# BUTTON_BREAKOUT.net
KiCad netlist of a schematic drawn in EAGLE
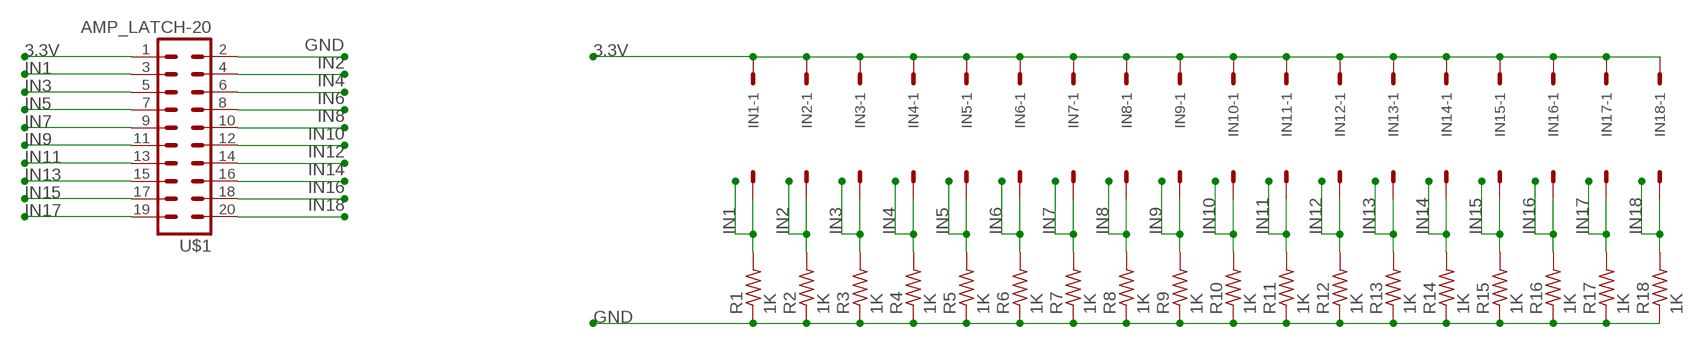
[diagram p0: schematic, sheet 1]

(export (version "E")
  (design (tool "Eeschema 10.0.6"))
  (components
    (comp (ref "IN1")
      (value "C-GRID-02-70543")
      (footprint "eagle-import:70543-02")
      (libsource (lib "eagle-import") (part "C-GRID-02-70543"))
    )
    (comp (ref "IN2")
      (value "C-GRID-02-70543")
      (footprint "eagle-import:70543-02")
      (libsource (lib "eagle-import") (part "C-GRID-02-70543"))
    )
    (comp (ref "IN3")
      (value "C-GRID-02-70543")
      (footprint "eagle-import:70543-02")
      (libsource (lib "eagle-import") (part "C-GRID-02-70543"))
    )
    (comp (ref "IN4")
      (value "C-GRID-02-70543")
      (footprint "eagle-import:70543-02")
      (libsource (lib "eagle-import") (part "C-GRID-02-70543"))
    )
    (comp (ref "IN5")
      (value "C-GRID-02-70543")
      (footprint "eagle-import:70543-02")
      (libsource (lib "eagle-import") (part "C-GRID-02-70543"))
    )
    (comp (ref "IN6")
      (value "C-GRID-02-70543")
      (footprint "eagle-import:70543-02")
      (libsource (lib "eagle-import") (part "C-GRID-02-70543"))
    )
    (comp (ref "IN7")
      (value "C-GRID-02-70543")
      (footprint "eagle-import:70543-02")
      (libsource (lib "eagle-import") (part "C-GRID-02-70543"))
    )
    (comp (ref "IN8")
      (value "C-GRID-02-70543")
      (footprint "eagle-import:70543-02")
      (libsource (lib "eagle-import") (part "C-GRID-02-70543"))
    )
    (comp (ref "IN9")
      (value "C-GRID-02-70543")
      (footprint "eagle-import:70543-02")
      (libsource (lib "eagle-import") (part "C-GRID-02-70543"))
    )
    (comp (ref "IN10")
      (value "C-GRID-02-70543")
      (footprint "eagle-import:70543-02")
      (libsource (lib "eagle-import") (part "C-GRID-02-70543"))
    )
    (comp (ref "IN11")
      (value "C-GRID-02-70543")
      (footprint "eagle-import:70543-02")
      (libsource (lib "eagle-import") (part "C-GRID-02-70543"))
    )
    (comp (ref "IN12")
      (value "C-GRID-02-70543")
      (footprint "eagle-import:70543-02")
      (libsource (lib "eagle-import") (part "C-GRID-02-70543"))
    )
    (comp (ref "IN13")
      (value "C-GRID-02-70543")
      (footprint "eagle-import:70543-02")
      (libsource (lib "eagle-import") (part "C-GRID-02-70543"))
    )
    (comp (ref "IN14")
      (value "C-GRID-02-70543")
      (footprint "eagle-import:70543-02")
      (libsource (lib "eagle-import") (part "C-GRID-02-70543"))
    )
    (comp (ref "IN15")
      (value "C-GRID-02-70543")
      (footprint "eagle-import:70543-02")
      (libsource (lib "eagle-import") (part "C-GRID-02-70543"))
    )
    (comp (ref "IN16")
      (value "C-GRID-02-70543")
      (footprint "eagle-import:70543-02")
      (libsource (lib "eagle-import") (part "C-GRID-02-70543"))
    )
    (comp (ref "IN17")
      (value "C-GRID-02-70543")
      (footprint "eagle-import:70543-02")
      (libsource (lib "eagle-import") (part "C-GRID-02-70543"))
    )
    (comp (ref "IN18")
      (value "C-GRID-02-70543")
      (footprint "eagle-import:70543-02")
      (libsource (lib "eagle-import") (part "C-GRID-02-70543"))
    )
    (comp (ref "R1")
      (value "1K")
      (footprint "eagle-import:R1206")
      (libsource (lib "eagle-import") (part "R-US_R1206"))
    )
    (comp (ref "R2")
      (value "1K")
      (footprint "eagle-import:R1206")
      (libsource (lib "eagle-import") (part "R-US_R1206"))
    )
    (comp (ref "R3")
      (value "1K")
      (footprint "eagle-import:R1206")
      (libsource (lib "eagle-import") (part "R-US_R1206"))
    )
    (comp (ref "R4")
      (value "1K")
      (footprint "eagle-import:R1206")
      (libsource (lib "eagle-import") (part "R-US_R1206"))
    )
    (comp (ref "R5")
      (value "1K")
      (footprint "eagle-import:R1206")
      (libsource (lib "eagle-import") (part "R-US_R1206"))
    )
    (comp (ref "R6")
      (value "1K")
      (footprint "eagle-import:R1206")
      (libsource (lib "eagle-import") (part "R-US_R1206"))
    )
    (comp (ref "R7")
      (value "1K")
      (footprint "eagle-import:R1206")
      (libsource (lib "eagle-import") (part "R-US_R1206"))
    )
    (comp (ref "R8")
      (value "1K")
      (footprint "eagle-import:R1206")
      (libsource (lib "eagle-import") (part "R-US_R1206"))
    )
    (comp (ref "R9")
      (value "1K")
      (footprint "eagle-import:R1206")
      (libsource (lib "eagle-import") (part "R-US_R1206"))
    )
    (comp (ref "R10")
      (value "1K")
      (footprint "eagle-import:R1206")
      (libsource (lib "eagle-import") (part "R-US_R1206"))
    )
    (comp (ref "R11")
      (value "1K")
      (footprint "eagle-import:R1206")
      (libsource (lib "eagle-import") (part "R-US_R1206"))
    )
    (comp (ref "R12")
      (value "1K")
      (footprint "eagle-import:R1206")
      (libsource (lib "eagle-import") (part "R-US_R1206"))
    )
    (comp (ref "R13")
      (value "1K")
      (footprint "eagle-import:R1206")
      (libsource (lib "eagle-import") (part "R-US_R1206"))
    )
    (comp (ref "R14")
      (value "1K")
      (footprint "eagle-import:R1206")
      (libsource (lib "eagle-import") (part "R-US_R1206"))
    )
    (comp (ref "R15")
      (value "1K")
      (footprint "eagle-import:R1206")
      (libsource (lib "eagle-import") (part "R-US_R1206"))
    )
    (comp (ref "R16")
      (value "1K")
      (footprint "eagle-import:R1206")
      (libsource (lib "eagle-import") (part "R-US_R1206"))
    )
    (comp (ref "R17")
      (value "1K")
      (footprint "eagle-import:R1206")
      (libsource (lib "eagle-import") (part "R-US_R1206"))
    )
    (comp (ref "R18")
      (value "1K")
      (footprint "eagle-import:R1206")
      (libsource (lib "eagle-import") (part "R-US_R1206"))
    )
    (comp (ref "U$1")
      (value "AMP_LATCH-20")
      (footprint "eagle-import:MA10-2")
      (fields (field (name "PART_NUM") "5499160-1"))
      (libsource (lib "eagle-import") (part "AMP_LATCH-20"))
    )
  )
  (nets
    (net (code "1") (name "/3.3V") (class "Default")
      (node (ref "IN1") (pin "1") (pinfunction "S_1") (pintype "passive"))
      (node (ref "IN10") (pin "1") (pinfunction "S_1") (pintype "passive"))
      (node (ref "IN11") (pin "1") (pinfunction "S_1") (pintype "passive"))
      (node (ref "IN12") (pin "1") (pinfunction "S_1") (pintype "passive"))
      (node (ref "IN13") (pin "1") (pinfunction "S_1") (pintype "passive"))
      (node (ref "IN14") (pin "1") (pinfunction "S_1") (pintype "passive"))
      (node (ref "IN15") (pin "1") (pinfunction "S_1") (pintype "passive"))
      (node (ref "IN16") (pin "1") (pinfunction "S_1") (pintype "passive"))
      (node (ref "IN17") (pin "1") (pinfunction "S_1") (pintype "passive"))
      (node (ref "IN18") (pin "1") (pinfunction "S_1") (pintype "passive"))
      (node (ref "IN2") (pin "1") (pinfunction "S_1") (pintype "passive"))
      (node (ref "IN3") (pin "1") (pinfunction "S_1") (pintype "passive"))
      (node (ref "IN4") (pin "1") (pinfunction "S_1") (pintype "passive"))
      (node (ref "IN5") (pin "1") (pinfunction "S_1") (pintype "passive"))
      (node (ref "IN6") (pin "1") (pinfunction "S_1") (pintype "passive"))
      (node (ref "IN7") (pin "1") (pinfunction "S_1") (pintype "passive"))
      (node (ref "IN8") (pin "1") (pinfunction "S_1") (pintype "passive"))
      (node (ref "IN9") (pin "1") (pinfunction "S_1") (pintype "passive"))
      (node (ref "U$1") (pin "1") (pinfunction "1_1") (pintype "passive"))
    )
    (net (code "2") (name "/GND") (class "Default")
      (node (ref "R1") (pin "1") (pinfunction "1_1") (pintype "passive"))
      (node (ref "R10") (pin "1") (pinfunction "1_1") (pintype "passive"))
      (node (ref "R11") (pin "1") (pinfunction "1_1") (pintype "passive"))
      (node (ref "R12") (pin "1") (pinfunction "1_1") (pintype "passive"))
      (node (ref "R13") (pin "1") (pinfunction "1_1") (pintype "passive"))
      (node (ref "R14") (pin "1") (pinfunction "1_1") (pintype "passive"))
      (node (ref "R15") (pin "1") (pinfunction "1_1") (pintype "passive"))
      (node (ref "R16") (pin "1") (pinfunction "1_1") (pintype "passive"))
      (node (ref "R17") (pin "1") (pinfunction "1_1") (pintype "passive"))
      (node (ref "R18") (pin "1") (pinfunction "1_1") (pintype "passive"))
      (node (ref "R2") (pin "1") (pinfunction "1_1") (pintype "passive"))
      (node (ref "R3") (pin "1") (pinfunction "1_1") (pintype "passive"))
      (node (ref "R4") (pin "1") (pinfunction "1_1") (pintype "passive"))
      (node (ref "R5") (pin "1") (pinfunction "1_1") (pintype "passive"))
      (node (ref "R6") (pin "1") (pinfunction "1_1") (pintype "passive"))
      (node (ref "R7") (pin "1") (pinfunction "1_1") (pintype "passive"))
      (node (ref "R8") (pin "1") (pinfunction "1_1") (pintype "passive"))
      (node (ref "R9") (pin "1") (pinfunction "1_1") (pintype "passive"))
      (node (ref "U$1") (pin "2") (pinfunction "2_2") (pintype "passive"))
    )
    (net (code "3") (name "/IN1") (class "Default")
      (node (ref "IN1") (pin "2") (pinfunction "S_2") (pintype "passive"))
      (node (ref "R1") (pin "2") (pinfunction "2_2") (pintype "passive"))
      (node (ref "U$1") (pin "3") (pinfunction "3_3") (pintype "passive"))
    )
    (net (code "4") (name "/IN2") (class "Default")
      (node (ref "IN2") (pin "2") (pinfunction "S_2") (pintype "passive"))
      (node (ref "R2") (pin "2") (pinfunction "2_2") (pintype "passive"))
      (node (ref "U$1") (pin "4") (pinfunction "4_4") (pintype "passive"))
    )
    (net (code "5") (name "/IN3") (class "Default")
      (node (ref "IN3") (pin "2") (pinfunction "S_2") (pintype "passive"))
      (node (ref "R3") (pin "2") (pinfunction "2_2") (pintype "passive"))
      (node (ref "U$1") (pin "5") (pinfunction "5_5") (pintype "passive"))
    )
    (net (code "6") (name "/IN4") (class "Default")
      (node (ref "IN4") (pin "2") (pinfunction "S_2") (pintype "passive"))
      (node (ref "R4") (pin "2") (pinfunction "2_2") (pintype "passive"))
      (node (ref "U$1") (pin "6") (pinfunction "6_6") (pintype "passive"))
    )
    (net (code "7") (name "/IN5") (class "Default")
      (node (ref "IN5") (pin "2") (pinfunction "S_2") (pintype "passive"))
      (node (ref "R5") (pin "2") (pinfunction "2_2") (pintype "passive"))
      (node (ref "U$1") (pin "7") (pinfunction "7_7") (pintype "passive"))
    )
    (net (code "8") (name "/IN6") (class "Default")
      (node (ref "IN6") (pin "2") (pinfunction "S_2") (pintype "passive"))
      (node (ref "R6") (pin "2") (pinfunction "2_2") (pintype "passive"))
      (node (ref "U$1") (pin "8") (pinfunction "8_8") (pintype "passive"))
    )
    (net (code "9") (name "/IN7") (class "Default")
      (node (ref "IN7") (pin "2") (pinfunction "S_2") (pintype "passive"))
      (node (ref "R7") (pin "2") (pinfunction "2_2") (pintype "passive"))
      (node (ref "U$1") (pin "9") (pinfunction "9_9") (pintype "passive"))
    )
    (net (code "10") (name "/IN8") (class "Default")
      (node (ref "IN8") (pin "2") (pinfunction "S_2") (pintype "passive"))
      (node (ref "R8") (pin "2") (pinfunction "2_2") (pintype "passive"))
      (node (ref "U$1") (pin "10") (pinfunction "10_10") (pintype "passive"))
    )
    (net (code "11") (name "/IN9") (class "Default")
      (node (ref "IN9") (pin "2") (pinfunction "S_2") (pintype "passive"))
      (node (ref "R9") (pin "2") (pinfunction "2_2") (pintype "passive"))
      (node (ref "U$1") (pin "11") (pinfunction "11_11") (pintype "passive"))
    )
    (net (code "12") (name "/IN10") (class "Default")
      (node (ref "IN10") (pin "2") (pinfunction "S_2") (pintype "passive"))
      (node (ref "R10") (pin "2") (pinfunction "2_2") (pintype "passive"))
      (node (ref "U$1") (pin "12") (pinfunction "12_12") (pintype "passive"))
    )
    (net (code "13") (name "/IN11") (class "Default")
      (node (ref "IN11") (pin "2") (pinfunction "S_2") (pintype "passive"))
      (node (ref "R11") (pin "2") (pinfunction "2_2") (pintype "passive"))
      (node (ref "U$1") (pin "13") (pinfunction "13_13") (pintype "passive"))
    )
    (net (code "14") (name "/IN12") (class "Default")
      (node (ref "IN12") (pin "2") (pinfunction "S_2") (pintype "passive"))
      (node (ref "R12") (pin "2") (pinfunction "2_2") (pintype "passive"))
      (node (ref "U$1") (pin "14") (pinfunction "14_14") (pintype "passive"))
    )
    (net (code "15") (name "/IN13") (class "Default")
      (node (ref "IN13") (pin "2") (pinfunction "S_2") (pintype "passive"))
      (node (ref "R13") (pin "2") (pinfunction "2_2") (pintype "passive"))
      (node (ref "U$1") (pin "15") (pinfunction "15_15") (pintype "passive"))
    )
    (net (code "16") (name "/IN14") (class "Default")
      (node (ref "IN14") (pin "2") (pinfunction "S_2") (pintype "passive"))
      (node (ref "R14") (pin "2") (pinfunction "2_2") (pintype "passive"))
      (node (ref "U$1") (pin "16") (pinfunction "16_16") (pintype "passive"))
    )
    (net (code "17") (name "/IN15") (class "Default")
      (node (ref "IN15") (pin "2") (pinfunction "S_2") (pintype "passive"))
      (node (ref "R15") (pin "2") (pinfunction "2_2") (pintype "passive"))
      (node (ref "U$1") (pin "17") (pinfunction "17_17") (pintype "passive"))
    )
    (net (code "18") (name "/IN16") (class "Default")
      (node (ref "IN16") (pin "2") (pinfunction "S_2") (pintype "passive"))
      (node (ref "R16") (pin "2") (pinfunction "2_2") (pintype "passive"))
      (node (ref "U$1") (pin "18") (pinfunction "18_18") (pintype "passive"))
    )
    (net (code "19") (name "/IN17") (class "Default")
      (node (ref "IN17") (pin "2") (pinfunction "S_2") (pintype "passive"))
      (node (ref "R17") (pin "2") (pinfunction "2_2") (pintype "passive"))
      (node (ref "U$1") (pin "19") (pinfunction "19_19") (pintype "passive"))
    )
    (net (code "20") (name "/IN18") (class "Default")
      (node (ref "IN18") (pin "2") (pinfunction "S_2") (pintype "passive"))
      (node (ref "R18") (pin "2") (pinfunction "2_2") (pintype "passive"))
      (node (ref "U$1") (pin "20") (pinfunction "20_20") (pintype "passive"))
    )
  )
)
